# Sonar_Power_Schematic_LT1117.net
KiCad netlist of a schematic drawn in EAGLE
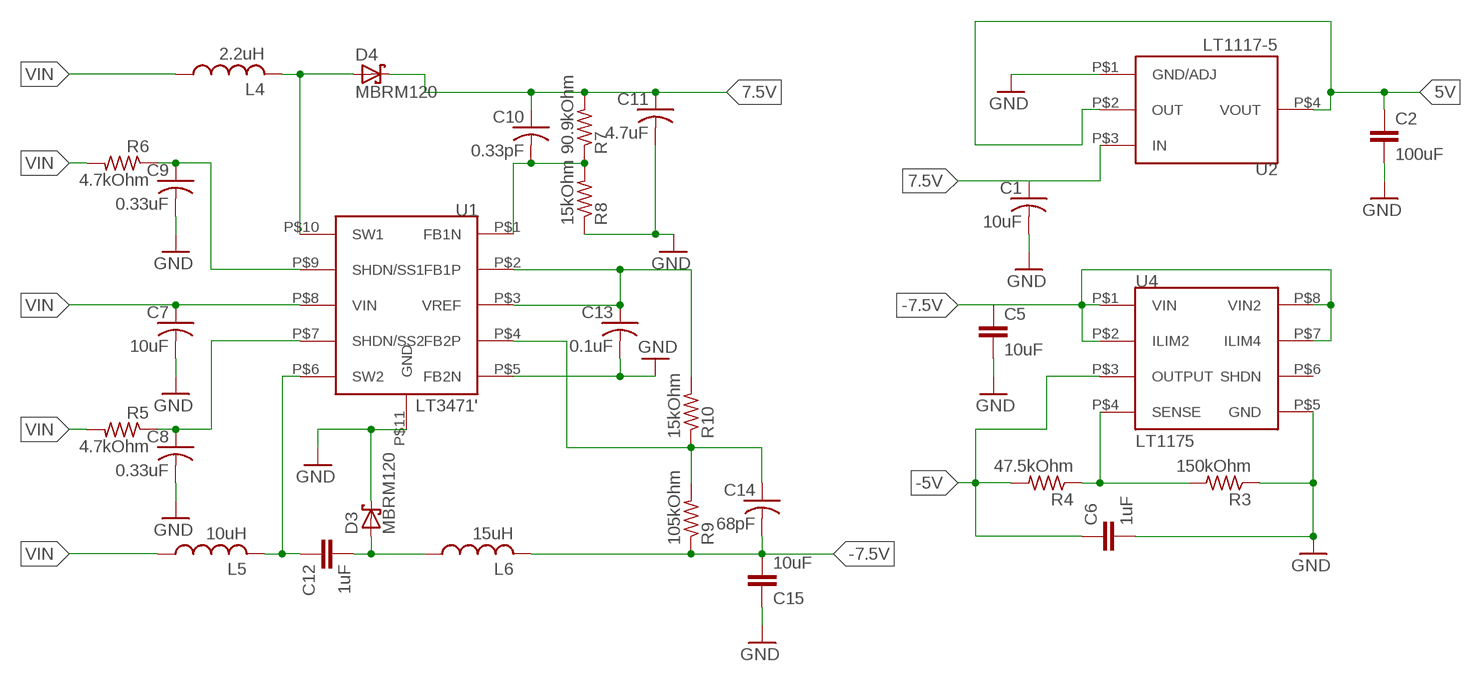
[diagram p0: schematic, sheet 1]

(export (version "E")
  (design (tool "Eeschema 10.0.6"))
  (components
    (comp (ref "C1")
      (value "10uF")
      (footprint "eagle-import:C0603")
      (libsource (lib "eagle-import") (part "C-USC0603"))
    )
    (comp (ref "C2")
      (value "100uF")
      (footprint "eagle-import:C1210")
      (libsource (lib "eagle-import") (part "C-EUC1210"))
    )
    (comp (ref "C5")
      (value "10uF")
      (footprint "eagle-import:C0603")
      (libsource (lib "eagle-import") (part "C-EUC0603"))
    )
    (comp (ref "C6")
      (value "1uF")
      (footprint "eagle-import:C1206")
      (libsource (lib "eagle-import") (part "C-EUC1206"))
    )
    (comp (ref "C7")
      (value "10uF")
      (footprint "eagle-import:C0603")
      (libsource (lib "eagle-import") (part "C-USC0603"))
    )
    (comp (ref "C8")
      (value "0.33uF")
      (footprint "eagle-import:C0603")
      (libsource (lib "eagle-import") (part "C-USC0603"))
    )
    (comp (ref "C9")
      (value "0.33uF")
      (footprint "eagle-import:C0603")
      (libsource (lib "eagle-import") (part "C-USC0603"))
    )
    (comp (ref "C10")
      (value "0.33pF")
      (footprint "eagle-import:C0603")
      (libsource (lib "eagle-import") (part "C-USC0603"))
    )
    (comp (ref "C11")
      (value "4.7uF")
      (footprint "eagle-import:C0603")
      (libsource (lib "eagle-import") (part "C-USC0603"))
    )
    (comp (ref "C12")
      (value "1uF")
      (footprint "eagle-import:C1206")
      (libsource (lib "eagle-import") (part "C-EUC1206"))
    )
    (comp (ref "C13")
      (value "0.1uF")
      (footprint "eagle-import:C0603")
      (libsource (lib "eagle-import") (part "C-USC0603"))
    )
    (comp (ref "C14")
      (value "68pF")
      (footprint "eagle-import:C0603")
      (libsource (lib "eagle-import") (part "C-USC0603"))
    )
    (comp (ref "C15")
      (value "10uF")
      (footprint "eagle-import:C0603")
      (libsource (lib "eagle-import") (part "C-EUC0603"))
    )
    (comp (ref "D3")
      (value "MBRM120")
      (footprint "eagle-import:DO-216AA")
      (libsource (lib "eagle-import") (part "MBRM120"))
    )
    (comp (ref "D4")
      (value "MBRM120")
      (footprint "eagle-import:DO-216AA")
      (libsource (lib "eagle-import") (part "MBRM120"))
    )
    (comp (ref "L4")
      (value "2.2uH")
      (footprint "eagle-import:NS4.9X4.9")
      (libsource (lib "eagle-import") (part "LQH5BPN2R2N38L"))
    )
    (comp (ref "L5")
      (value "10uH")
      (footprint "eagle-import:NS5X5")
      (libsource (lib "eagle-import") (part "VLS5045EX-100M2"))
    )
    (comp (ref "L6")
      (value "15uH")
      (footprint "eagle-import:NS5X5")
      (libsource (lib "eagle-import") (part "VLS5045EX-150M-CA1"))
    )
    (comp (ref "R3")
      (value "150kOhm")
      (footprint "eagle-import:R0603")
      (libsource (lib "eagle-import") (part "R-US_R0603"))
    )
    (comp (ref "R4")
      (value "47.5kOhm")
      (footprint "eagle-import:R0603")
      (libsource (lib "eagle-import") (part "R-US_R0603"))
    )
    (comp (ref "R5")
      (value "4.7kOhm")
      (footprint "eagle-import:R0603")
      (libsource (lib "eagle-import") (part "R-US_R0603"))
    )
    (comp (ref "R6")
      (value "4.7kOhm")
      (footprint "eagle-import:R0603")
      (libsource (lib "eagle-import") (part "R-US_R0603"))
    )
    (comp (ref "R7")
      (value "90.9kOhm")
      (footprint "eagle-import:R0603")
      (libsource (lib "eagle-import") (part "R-US_R0603"))
    )
    (comp (ref "R8")
      (value "15kOhm")
      (footprint "eagle-import:R0603")
      (libsource (lib "eagle-import") (part "R-US_R0603"))
    )
    (comp (ref "R9")
      (value "105kOhm")
      (footprint "eagle-import:R0603")
      (libsource (lib "eagle-import") (part "R-US_R0603"))
    )
    (comp (ref "R10")
      (value "15kOhm")
      (footprint "eagle-import:R0603")
      (libsource (lib "eagle-import") (part "R-US_R0603"))
    )
    (comp (ref "U1")
      (value "LT3471'")
      (footprint "eagle-import:10-WFDFN")
      (libsource (lib "eagle-import") (part "LT3471'"))
    )
    (comp (ref "U2")
      (value "LT1117-5")
      (footprint "eagle-import:SOT233-3")
      (libsource (lib "eagle-import") (part "LT1117-5"))
    )
    (comp (ref "U4")
      (value "LT1175")
      (footprint "eagle-import:8-SOIC")
      (libsource (lib "eagle-import") (part "LT1175"))
    )
  )
  (nets
    (net (code "1") (name "-5V") (class "Default")
      (node (ref "C6") (pin "1") (pinfunction "1_1") (pintype "passive"))
      (node (ref "R4") (pin "2") (pinfunction "2_2") (pintype "passive"))
      (node (ref "U4") (pin "P$3") (pinfunction "OUTPUT_P$3") (pintype "bidirectional"))
    )
    (net (code "2") (name "-7.5V") (class "Default")
      (node (ref "C14") (pin "2") (pinfunction "2_2") (pintype "passive"))
      (node (ref "C15") (pin "2") (pinfunction "2_2") (pintype "passive"))
      (node (ref "C5") (pin "1") (pinfunction "1_1") (pintype "passive"))
      (node (ref "L6") (pin "P$2") (pinfunction "2_P$2") (pintype "passive"))
      (node (ref "R9") (pin "1") (pinfunction "1_1") (pintype "passive"))
      (node (ref "U4") (pin "P$1") (pinfunction "VIN_P$1") (pintype "power_in"))
      (node (ref "U4") (pin "P$2") (pinfunction "ILIM2_P$2") (pintype "bidirectional"))
      (node (ref "U4") (pin "P$7") (pinfunction "ILIM4_P$7") (pintype "bidirectional"))
      (node (ref "U4") (pin "P$8") (pinfunction "VIN2_P$8") (pintype "power_in"))
    )
    (net (code "3") (name "5V") (class "Default")
      (node (ref "C2") (pin "1") (pinfunction "1_1") (pintype "passive"))
      (node (ref "U2") (pin "P$2") (pinfunction "OUT_P$2") (pintype "bidirectional"))
      (node (ref "U2") (pin "P$4") (pinfunction "VOUT_P$4") (pintype "bidirectional"))
    )
    (net (code "4") (name "7.5V") (class "Default")
      (node (ref "C1") (pin "1") (pinfunction "1_1") (pintype "passive"))
      (node (ref "C10") (pin "1") (pinfunction "1_1") (pintype "passive"))
      (node (ref "C11") (pin "1") (pinfunction "1_1") (pintype "passive"))
      (node (ref "D4") (pin "P$1") (pinfunction "C_P$1") (pintype "passive"))
      (node (ref "R7") (pin "2") (pinfunction "2_2") (pintype "passive"))
      (node (ref "U2") (pin "P$3") (pinfunction "IN_P$3") (pintype "bidirectional"))
    )
    (net (code "5") (name "GND") (class "Default")
      (node (ref "C1") (pin "2") (pinfunction "2_2") (pintype "passive"))
      (node (ref "C11") (pin "2") (pinfunction "2_2") (pintype "passive"))
      (node (ref "C13") (pin "2") (pinfunction "2_2") (pintype "passive"))
      (node (ref "C15") (pin "1") (pinfunction "1_1") (pintype "passive"))
      (node (ref "C2") (pin "2") (pinfunction "2_2") (pintype "passive"))
      (node (ref "C5") (pin "2") (pinfunction "2_2") (pintype "passive"))
      (node (ref "C6") (pin "2") (pinfunction "2_2") (pintype "passive"))
      (node (ref "C7") (pin "2") (pinfunction "2_2") (pintype "passive"))
      (node (ref "C8") (pin "2") (pinfunction "2_2") (pintype "passive"))
      (node (ref "C9") (pin "2") (pinfunction "2_2") (pintype "passive"))
      (node (ref "D3") (pin "P$1") (pinfunction "C_P$1") (pintype "passive"))
      (node (ref "R3") (pin "1") (pinfunction "1_1") (pintype "passive"))
      (node (ref "R8") (pin "1") (pinfunction "1_1") (pintype "passive"))
      (node (ref "U1") (pin "P$11") (pinfunction "GND_P$11") (pintype "power_in"))
      (node (ref "U1") (pin "P$5") (pinfunction "FB2N_P$5") (pintype "bidirectional"))
      (node (ref "U2") (pin "P$1") (pinfunction "GND/ADJ_P$1") (pintype "bidirectional"))
      (node (ref "U4") (pin "P$5") (pinfunction "GND_P$5") (pintype "power_in"))
    )
    (net (code "6") (name "Net-(D3-A)") (class "Default")
      (node (ref "C12") (pin "2") (pinfunction "2_2") (pintype "passive"))
      (node (ref "D3") (pin "P$2") (pinfunction "A_P$2") (pintype "passive"))
      (node (ref "L6") (pin "P$1") (pinfunction "1_P$1") (pintype "passive"))
    )
    (net (code "7") (name "Net-(D4-A)") (class "Default")
      (node (ref "D4") (pin "P$2") (pinfunction "A_P$2") (pintype "passive"))
      (node (ref "L4") (pin "P$2") (pinfunction "2_P$2") (pintype "passive"))
      (node (ref "U1") (pin "P$10") (pinfunction "SW1_P$10") (pintype "bidirectional"))
    )
    (net (code "8") (name "Net-(L5-2)") (class "Default")
      (node (ref "C12") (pin "1") (pinfunction "1_1") (pintype "passive"))
      (node (ref "L5") (pin "P$2") (pinfunction "2_P$2") (pintype "passive"))
      (node (ref "U1") (pin "P$6") (pinfunction "SW2_P$6") (pintype "bidirectional"))
    )
    (net (code "9") (name "Net-(U1-FB1N)") (class "Default")
      (node (ref "C10") (pin "2") (pinfunction "2_2") (pintype "passive"))
      (node (ref "R7") (pin "1") (pinfunction "1_1") (pintype "passive"))
      (node (ref "R8") (pin "2") (pinfunction "2_2") (pintype "passive"))
      (node (ref "U1") (pin "P$1") (pinfunction "FB1N_P$1") (pintype "bidirectional"))
    )
    (net (code "10") (name "Net-(U1-FB1P)") (class "Default")
      (node (ref "C13") (pin "1") (pinfunction "1_1") (pintype "passive"))
      (node (ref "R10") (pin "2") (pinfunction "2_2") (pintype "passive"))
      (node (ref "U1") (pin "P$2") (pinfunction "FB1P_P$2") (pintype "bidirectional"))
      (node (ref "U1") (pin "P$3") (pinfunction "VREF_P$3") (pintype "power_in"))
    )
    (net (code "11") (name "Net-(U1-FB2P)") (class "Default")
      (node (ref "C14") (pin "1") (pinfunction "1_1") (pintype "passive"))
      (node (ref "R10") (pin "1") (pinfunction "1_1") (pintype "passive"))
      (node (ref "R9") (pin "2") (pinfunction "2_2") (pintype "passive"))
      (node (ref "U1") (pin "P$4") (pinfunction "FB2P_P$4") (pintype "bidirectional"))
    )
    (net (code "12") (name "Net-(U1-SHDN{slash}SS1)") (class "Default")
      (node (ref "C9") (pin "1") (pinfunction "1_1") (pintype "passive"))
      (node (ref "R6") (pin "1") (pinfunction "1_1") (pintype "passive"))
      (node (ref "U1") (pin "P$9") (pinfunction "SHDN/SS1_P$9") (pintype "bidirectional"))
    )
    (net (code "13") (name "Net-(U1-SHDN{slash}SS2)") (class "Default")
      (node (ref "C8") (pin "1") (pinfunction "1_1") (pintype "passive"))
      (node (ref "R5") (pin "1") (pinfunction "1_1") (pintype "passive"))
      (node (ref "U1") (pin "P$7") (pinfunction "SHDN/SS2_P$7") (pintype "bidirectional"))
    )
    (net (code "14") (name "Net-(U4-SENSE)") (class "Default")
      (node (ref "R3") (pin "2") (pinfunction "2_2") (pintype "passive"))
      (node (ref "R4") (pin "1") (pinfunction "1_1") (pintype "passive"))
      (node (ref "U4") (pin "P$4") (pinfunction "SENSE_P$4") (pintype "bidirectional"))
    )
    (net (code "15") (name "VIN") (class "Default")
      (node (ref "C7") (pin "1") (pinfunction "1_1") (pintype "passive"))
      (node (ref "L4") (pin "P$1") (pinfunction "1_P$1") (pintype "passive"))
      (node (ref "L5") (pin "P$1") (pinfunction "1_P$1") (pintype "passive"))
      (node (ref "R5") (pin "2") (pinfunction "2_2") (pintype "passive"))
      (node (ref "R6") (pin "2") (pinfunction "2_2") (pintype "passive"))
      (node (ref "U1") (pin "P$8") (pinfunction "VIN_P$8") (pintype "power_in"))
    )
    (net (code "16") (name "unconnected-(U4-SHDN-PadP$6)") (class "Default")
      (node (ref "U4") (pin "P$6") (pinfunction "SHDN_P$6") (pintype "bidirectional"))
    )
  )
)
